# programmer.net
KiCad netlist of a schematic drawn in EAGLE
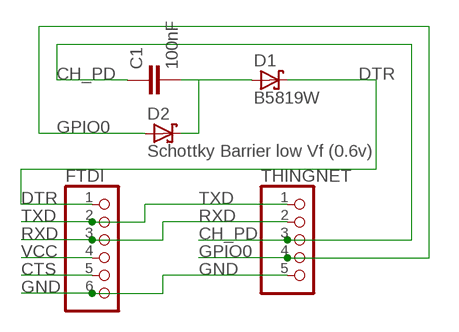
[diagram p0: schematic, sheet 1]

(export (version "E")
  (design (tool "Eeschema 10.0.6"))
  (components
    (comp (ref "C1")
      (value "100nF")
      (footprint "eagle-import:C025-024X044")
      (libsource (lib "eagle-import") (part "C-EU025-024X044"))
    )
    (comp (ref "D1")
      (value "B5819W")
      (footprint "eagle-import:DO35-7")
      (libsource (lib "eagle-import") (part "SCHOTTKY-DIODEDO35-7"))
    )
    (comp (ref "D2")
      (value "Schottky Barrier low Vf (0.6v)")
      (footprint "eagle-import:DO35-7")
      (libsource (lib "eagle-import") (part "SCHOTTKY-DIODEDO35-7"))
    )
    (comp (ref "FTDI")
      (value "PINHD-1X6")
      (footprint "eagle-import:1X06")
      (libsource (lib "eagle-import") (part "PINHD-1X6"))
    )
    (comp (ref "THINGNET")
      (value "PINHD-1X5")
      (footprint "eagle-import:1X05")
      (libsource (lib "eagle-import") (part "PINHD-1X5"))
    )
  )
  (nets
    (net (code "1") (name "/CH_PD") (class "Default")
      (node (ref "C1") (pin "1") (pinfunction "1_1") (pintype "passive"))
      (node (ref "THINGNET") (pin "3") (pinfunction "3_3") (pintype "passive"))
    )
    (net (code "2") (name "/CTS") (class "Default")
      (node (ref "FTDI") (pin "5") (pinfunction "5_5") (pintype "passive"))
    )
    (net (code "3") (name "/DTR") (class "Default")
      (node (ref "D1") (pin "C") (pinfunction "C_C") (pintype "passive"))
      (node (ref "FTDI") (pin "1") (pinfunction "1_1") (pintype "passive"))
    )
    (net (code "4") (name "/GND") (class "Default")
      (node (ref "FTDI") (pin "6") (pinfunction "6_6") (pintype "passive"))
      (node (ref "THINGNET") (pin "5") (pinfunction "5_5") (pintype "passive"))
    )
    (net (code "5") (name "/GPIO0") (class "Default")
      (node (ref "D2") (pin "A") (pinfunction "A_A") (pintype "passive"))
      (node (ref "THINGNET") (pin "4") (pinfunction "4_4") (pintype "passive"))
    )
    (net (code "6") (name "/RXD") (class "Default")
      (node (ref "FTDI") (pin "3") (pinfunction "3_3") (pintype "passive"))
      (node (ref "THINGNET") (pin "2") (pinfunction "2_2") (pintype "passive"))
    )
    (net (code "7") (name "/TXD") (class "Default")
      (node (ref "FTDI") (pin "2") (pinfunction "2_2") (pintype "passive"))
      (node (ref "THINGNET") (pin "1") (pinfunction "1_1") (pintype "passive"))
    )
    (net (code "8") (name "/VCC") (class "Default")
      (node (ref "FTDI") (pin "4") (pinfunction "4_4") (pintype "passive"))
    )
    (net (code "9") (name "Net-(C1-Pad2)") (class "Default")
      (node (ref "C1") (pin "2") (pinfunction "2_2") (pintype "passive"))
      (node (ref "D1") (pin "A") (pinfunction "A_A") (pintype "passive"))
      (node (ref "D2") (pin "C") (pinfunction "C_C") (pintype "passive"))
    )
  )
)
